# scanner154.net
KiCad netlist of a schematic drawn in EAGLE
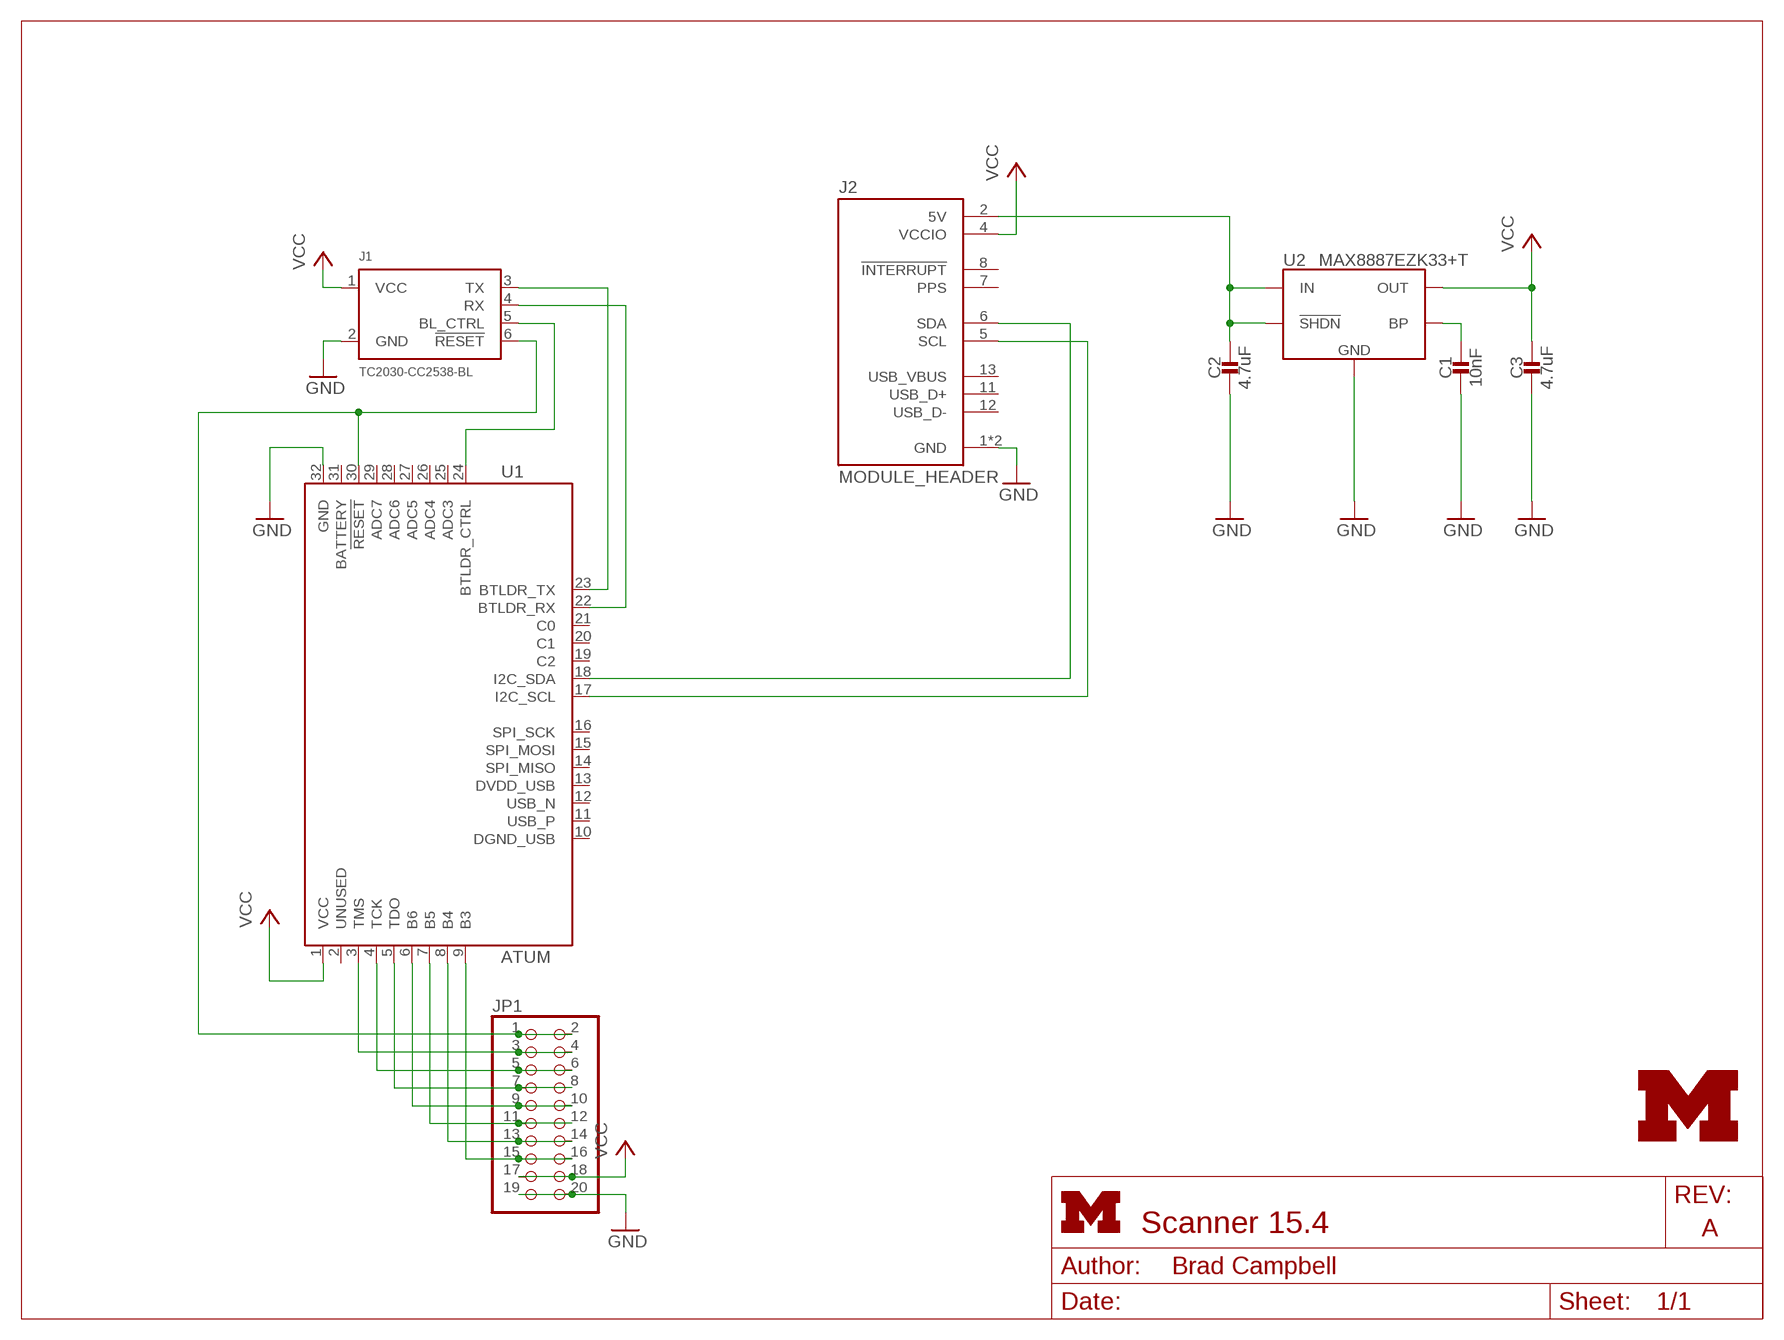
[diagram p0: schematic, sheet 1]

(export (version "E")
  (design (tool "Eeschema 10.0.6"))
  (components
    (comp (ref "C1")
      (value "10nF")
      (footprint "eagle-import:0603_CAP")
      (libsource (lib "eagle-import") (part "CAPACITOR0603_CAP"))
    )
    (comp (ref "C2")
      (value "4.7uF")
      (footprint "eagle-import:0603_CAP")
      (libsource (lib "eagle-import") (part "CAPACITOR0603_CAP"))
    )
    (comp (ref "C3")
      (value "4.7uF")
      (footprint "eagle-import:0603_CAP")
      (libsource (lib "eagle-import") (part "CAPACITOR0603_CAP"))
    )
    (comp (ref "J1")
      (value "TC2030-CC2538-BL")
      (footprint "eagle-import:TC2030-IDC")
      (libsource (lib "eagle-import") (part "TC2030-CC2538-BL"))
    )
    (comp (ref "J2")
      (value "MODULE_HEADER")
      (footprint "eagle-import:HEADER_14PIN")
      (libsource (lib "eagle-import") (part "MODULE_HEADER"))
    )
    (comp (ref "JP1")
      (value "PINHD-2X10")
      (footprint "eagle-import:2X10")
      (libsource (lib "eagle-import") (part "PINHD-2X10"))
    )
    (comp (ref "LOGO2")
      (value "UMICH_SOLID_HUGE")
      (footprint "eagle-import:UMICH_SOLID_500MIL")
      (libsource (lib "eagle-import") (part "UMICH_SOLID_HUGE"))
    )
    (comp (ref "U1")
      (value "ATUM")
      (footprint "eagle-import:ATUM")
      (libsource (lib "eagle-import") (part "ATUM"))
    )
    (comp (ref "U2")
      (value "MAX8887EZK33+T")
      (footprint "eagle-import:SOT-23-5")
      (libsource (lib "eagle-import") (part "MAX8887EZK33+T"))
    )
  )
  (nets
    (net (code "1") (name "GND") (class "Default")
      (node (ref "C1") (pin "2") (pinfunction "2_2") (pintype "bidirectional"))
      (node (ref "C2") (pin "2") (pinfunction "2_2") (pintype "bidirectional"))
      (node (ref "C3") (pin "2") (pinfunction "2_2") (pintype "bidirectional"))
      (node (ref "J1") (pin "2") (pinfunction "GND_2") (pintype "bidirectional"))
      (node (ref "J2") (pin "1") (pinfunction "GND_1") (pintype "bidirectional"))
      (node (ref "J2") (pin "14") (pinfunction "GND_14") (pintype "bidirectional"))
      (node (ref "JP1") (pin "19") (pinfunction "19_19") (pintype "passive"))
      (node (ref "JP1") (pin "20") (pinfunction "20_20") (pintype "passive"))
      (node (ref "U1") (pin "32") (pinfunction "GND_32") (pintype "bidirectional"))
      (node (ref "U2") (pin "2") (pinfunction "GND_2") (pintype "bidirectional"))
    )
    (net (code "2") (name "Net-(J1-BL_CTRL)") (class "Default")
      (node (ref "J1") (pin "5") (pinfunction "BL_CTRL_5") (pintype "bidirectional"))
      (node (ref "U1") (pin "24") (pinfunction "BTLDR_CTRL_24") (pintype "bidirectional"))
    )
    (net (code "3") (name "Net-(J1-RX)") (class "Default")
      (node (ref "J1") (pin "4") (pinfunction "RX_4") (pintype "bidirectional"))
      (node (ref "U1") (pin "22") (pinfunction "BTLDR_RX_22") (pintype "bidirectional"))
    )
    (net (code "4") (name "Net-(J1-TX)") (class "Default")
      (node (ref "J1") (pin "3") (pinfunction "TX_3") (pintype "bidirectional"))
      (node (ref "U1") (pin "23") (pinfunction "BTLDR_TX_23") (pintype "bidirectional"))
    )
    (net (code "5") (name "Net-(J1-~{RESET})") (class "Default")
      (node (ref "J1") (pin "6") (pinfunction "~{RESET}_6") (pintype "bidirectional"))
      (node (ref "JP1") (pin "1") (pinfunction "1_1") (pintype "passive"))
      (node (ref "JP1") (pin "2") (pinfunction "2_2") (pintype "passive"))
      (node (ref "U1") (pin "30") (pinfunction "~{RESET}_30") (pintype "bidirectional"))
    )
    (net (code "6") (name "Net-(J2-5V)") (class "Default")
      (node (ref "C2") (pin "1") (pinfunction "1_1") (pintype "bidirectional"))
      (node (ref "J2") (pin "2") (pinfunction "5V_2") (pintype "bidirectional"))
      (node (ref "U2") (pin "1") (pinfunction "IN_1") (pintype "bidirectional"))
      (node (ref "U2") (pin "3") (pinfunction "~{SHDN}_3") (pintype "bidirectional"))
    )
    (net (code "7") (name "Net-(J2-SCL)") (class "Default")
      (node (ref "J2") (pin "5") (pinfunction "SCL_5") (pintype "bidirectional"))
      (node (ref "U1") (pin "17") (pinfunction "I2C_SCL_17") (pintype "bidirectional"))
    )
    (net (code "8") (name "Net-(J2-SDA)") (class "Default")
      (node (ref "J2") (pin "6") (pinfunction "SDA_6") (pintype "bidirectional"))
      (node (ref "U1") (pin "18") (pinfunction "I2C_SDA_18") (pintype "bidirectional"))
    )
    (net (code "9") (name "Net-(U1-B3)") (class "Default")
      (node (ref "JP1") (pin "15") (pinfunction "15_15") (pintype "passive"))
      (node (ref "JP1") (pin "16") (pinfunction "16_16") (pintype "passive"))
      (node (ref "U1") (pin "9") (pinfunction "B3_9") (pintype "bidirectional"))
    )
    (net (code "10") (name "Net-(U1-B4)") (class "Default")
      (node (ref "JP1") (pin "13") (pinfunction "13_13") (pintype "passive"))
      (node (ref "JP1") (pin "14") (pinfunction "14_14") (pintype "passive"))
      (node (ref "U1") (pin "8") (pinfunction "B4_8") (pintype "bidirectional"))
    )
    (net (code "11") (name "Net-(U1-B5)") (class "Default")
      (node (ref "JP1") (pin "11") (pinfunction "11_11") (pintype "passive"))
      (node (ref "JP1") (pin "12") (pinfunction "12_12") (pintype "passive"))
      (node (ref "U1") (pin "7") (pinfunction "B5_7") (pintype "bidirectional"))
    )
    (net (code "12") (name "Net-(U1-B6)") (class "Default")
      (node (ref "JP1") (pin "10") (pinfunction "10_10") (pintype "passive"))
      (node (ref "JP1") (pin "9") (pinfunction "9_9") (pintype "passive"))
      (node (ref "U1") (pin "6") (pinfunction "B6_6") (pintype "bidirectional"))
    )
    (net (code "13") (name "Net-(U1-TCK)") (class "Default")
      (node (ref "JP1") (pin "5") (pinfunction "5_5") (pintype "passive"))
      (node (ref "JP1") (pin "6") (pinfunction "6_6") (pintype "passive"))
      (node (ref "U1") (pin "4") (pinfunction "TCK_4") (pintype "bidirectional"))
    )
    (net (code "14") (name "Net-(U1-TDO)") (class "Default")
      (node (ref "JP1") (pin "7") (pinfunction "7_7") (pintype "passive"))
      (node (ref "JP1") (pin "8") (pinfunction "8_8") (pintype "passive"))
      (node (ref "U1") (pin "5") (pinfunction "TDO_5") (pintype "bidirectional"))
    )
    (net (code "15") (name "Net-(U1-TMS)") (class "Default")
      (node (ref "JP1") (pin "3") (pinfunction "3_3") (pintype "passive"))
      (node (ref "JP1") (pin "4") (pinfunction "4_4") (pintype "passive"))
      (node (ref "U1") (pin "3") (pinfunction "TMS_3") (pintype "bidirectional"))
    )
    (net (code "16") (name "Net-(U2-BP)") (class "Default")
      (node (ref "C1") (pin "1") (pinfunction "1_1") (pintype "bidirectional"))
      (node (ref "U2") (pin "4") (pinfunction "BP_4") (pintype "bidirectional"))
    )
    (net (code "17") (name "VCC") (class "Default")
      (node (ref "C3") (pin "1") (pinfunction "1_1") (pintype "bidirectional"))
      (node (ref "J1") (pin "1") (pinfunction "VCC_1") (pintype "bidirectional"))
      (node (ref "J2") (pin "4") (pinfunction "VCCIO_4") (pintype "bidirectional"))
      (node (ref "JP1") (pin "17") (pinfunction "17_17") (pintype "passive"))
      (node (ref "JP1") (pin "18") (pinfunction "18_18") (pintype "passive"))
      (node (ref "U1") (pin "1") (pinfunction "VCC_1") (pintype "bidirectional"))
      (node (ref "U2") (pin "5") (pinfunction "OUT_5") (pintype "bidirectional"))
    )
    (net (code "18") (name "unconnected-(J2-PPS-Pad7)") (class "Default")
      (node (ref "J2") (pin "7") (pinfunction "PPS_7") (pintype "bidirectional"))
    )
    (net (code "19") (name "unconnected-(J2-USB_D+-Pad11)") (class "Default")
      (node (ref "J2") (pin "11") (pinfunction "USB_D+_11") (pintype "bidirectional"))
    )
    (net (code "20") (name "unconnected-(J2-USB_D--Pad12)") (class "Default")
      (node (ref "J2") (pin "12") (pinfunction "USB_D-_12") (pintype "bidirectional"))
    )
    (net (code "21") (name "unconnected-(J2-USB_VBUS-Pad13)") (class "Default")
      (node (ref "J2") (pin "13") (pinfunction "USB_VBUS_13") (pintype "bidirectional"))
    )
    (net (code "22") (name "unconnected-(J2-~{INTERRUPT}-Pad8)") (class "Default")
      (node (ref "J2") (pin "8") (pinfunction "~{INTERRUPT}_8") (pintype "bidirectional"))
    )
    (net (code "23") (name "unconnected-(U1-ADC3-Pad25)") (class "Default")
      (node (ref "U1") (pin "25") (pinfunction "ADC3_25") (pintype "bidirectional"))
    )
    (net (code "24") (name "unconnected-(U1-ADC4-Pad26)") (class "Default")
      (node (ref "U1") (pin "26") (pinfunction "ADC4_26") (pintype "bidirectional"))
    )
    (net (code "25") (name "unconnected-(U1-ADC5-Pad27)") (class "Default")
      (node (ref "U1") (pin "27") (pinfunction "ADC5_27") (pintype "bidirectional"))
    )
    (net (code "26") (name "unconnected-(U1-ADC6-Pad28)") (class "Default")
      (node (ref "U1") (pin "28") (pinfunction "ADC6_28") (pintype "bidirectional"))
    )
    (net (code "27") (name "unconnected-(U1-ADC7-Pad29)") (class "Default")
      (node (ref "U1") (pin "29") (pinfunction "ADC7_29") (pintype "bidirectional"))
    )
    (net (code "28") (name "unconnected-(U1-BATTERY-Pad31)") (class "Default")
      (node (ref "U1") (pin "31") (pinfunction "BATTERY_31") (pintype "bidirectional"))
    )
    (net (code "29") (name "unconnected-(U1-C0-Pad21)") (class "Default")
      (node (ref "U1") (pin "21") (pinfunction "C0_21") (pintype "bidirectional"))
    )
    (net (code "30") (name "unconnected-(U1-C1-Pad20)") (class "Default")
      (node (ref "U1") (pin "20") (pinfunction "C1_20") (pintype "bidirectional"))
    )
    (net (code "31") (name "unconnected-(U1-C2-Pad19)") (class "Default")
      (node (ref "U1") (pin "19") (pinfunction "C2_19") (pintype "bidirectional"))
    )
    (net (code "32") (name "unconnected-(U1-DGND_USB-Pad10)") (class "Default")
      (node (ref "U1") (pin "10") (pinfunction "DGND_USB_10") (pintype "bidirectional"))
    )
    (net (code "33") (name "unconnected-(U1-DVDD_USB-Pad13)") (class "Default")
      (node (ref "U1") (pin "13") (pinfunction "DVDD_USB_13") (pintype "bidirectional"))
    )
    (net (code "34") (name "unconnected-(U1-SPI_MISO-Pad14)") (class "Default")
      (node (ref "U1") (pin "14") (pinfunction "SPI_MISO_14") (pintype "bidirectional"))
    )
    (net (code "35") (name "unconnected-(U1-SPI_MOSI-Pad15)") (class "Default")
      (node (ref "U1") (pin "15") (pinfunction "SPI_MOSI_15") (pintype "bidirectional"))
    )
    (net (code "36") (name "unconnected-(U1-SPI_SCK-Pad16)") (class "Default")
      (node (ref "U1") (pin "16") (pinfunction "SPI_SCK_16") (pintype "bidirectional"))
    )
    (net (code "37") (name "unconnected-(U1-UNUSED-Pad2)") (class "Default")
      (node (ref "U1") (pin "2") (pinfunction "UNUSED_2") (pintype "bidirectional"))
    )
    (net (code "38") (name "unconnected-(U1-USB_N-Pad12)") (class "Default")
      (node (ref "U1") (pin "12") (pinfunction "USB_N_12") (pintype "bidirectional"))
    )
    (net (code "39") (name "unconnected-(U1-USB_P-Pad11)") (class "Default")
      (node (ref "U1") (pin "11") (pinfunction "USB_P_11") (pintype "bidirectional"))
    )
  )
)
